# Sheet_1_MCU.net
KiCad netlist of a schematic drawn in Altium Designer
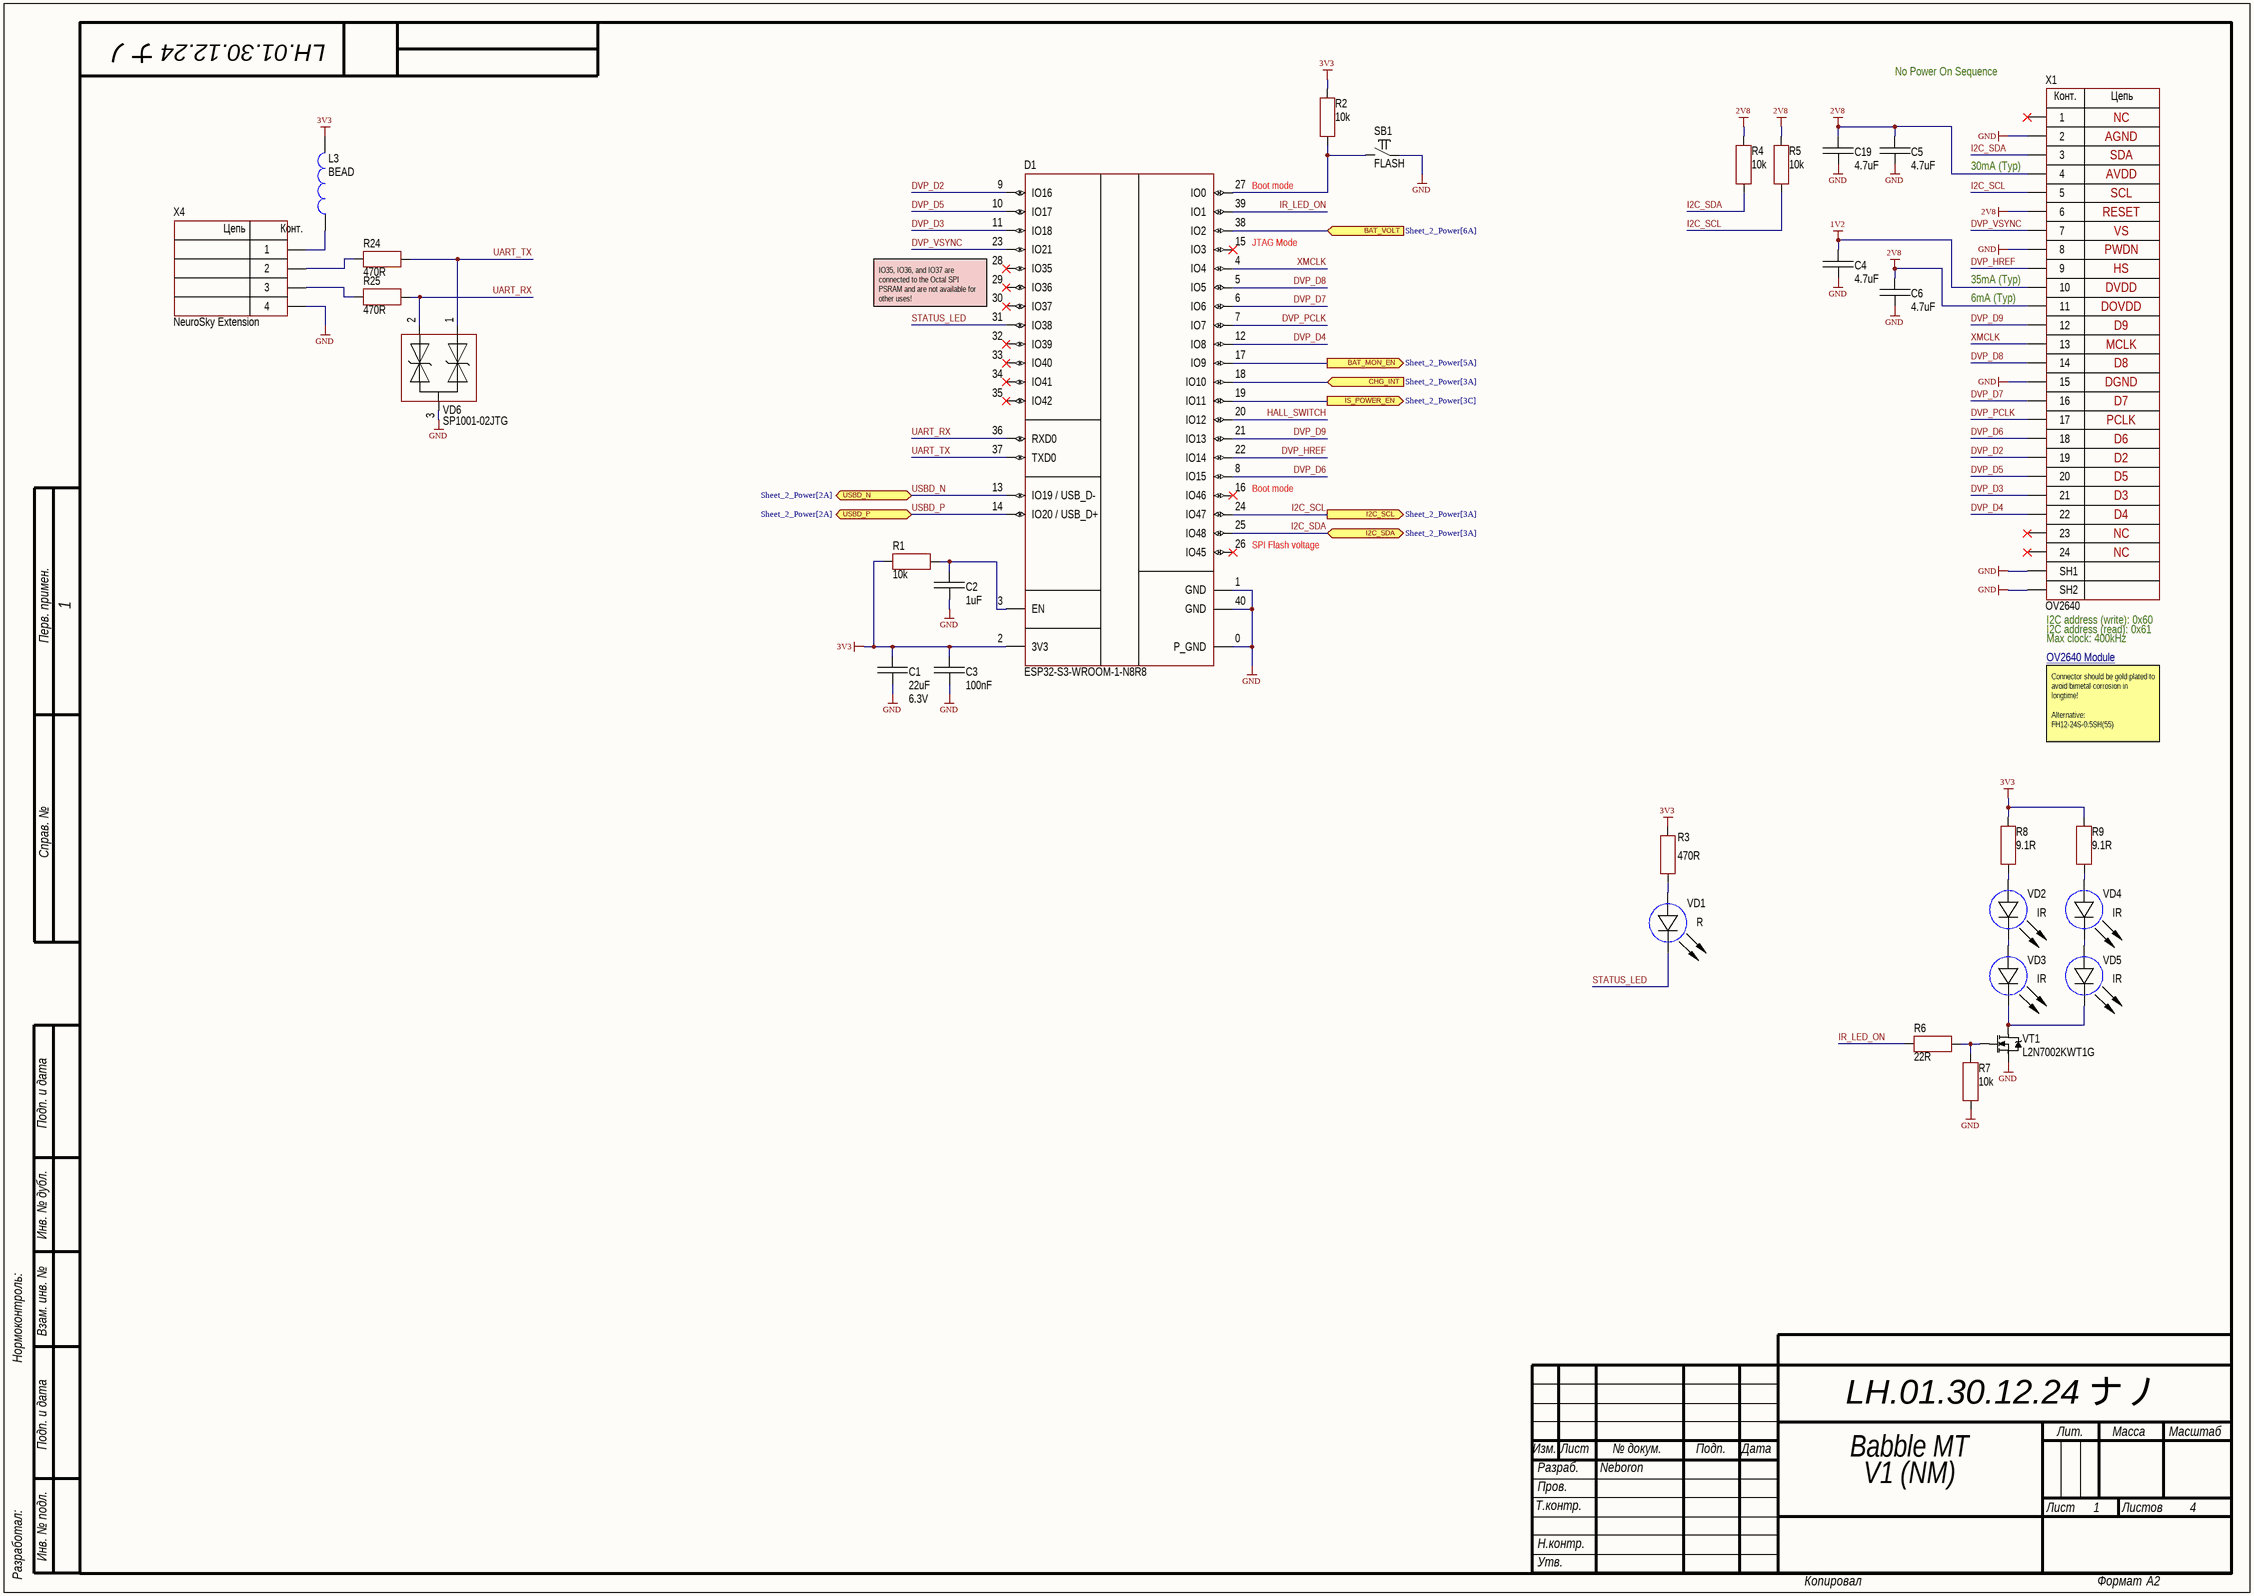
[diagram p0: Sheet_1_MCU.SchDoc]

(export (version "E")
  (design (tool "Eeschema 10.0.6"))
  (components
    (comp (ref "C1")
      (value "22uF")
      (footprint "CAP: 0603")
      (fields
        (field (name "MANUFACTURER") "Any")
        (field (name "VALUEMANUFACTURERPARTNUMBER") "Ceramic capacitor, 22uF, X5R, ±10%, 6.3V, 0603, -55...+125°C")
        (field (name "TOLERANCE") "±10%")
        (field (name "VOLTAGE") "6.3V")
      )
      (libsource (lib "capacitor") (part "Ceramic_0603"))
    )
    (comp (ref "C2")
      (value "1uF")
      (footprint "CAP: 0402")
      (fields
        (field (name "MANUFACTURER") "Any")
        (field (name "VALUEMANUFACTURERPARTNUMBER") "Ceramic capacitor, 1uF, X7R, ±10%, 6.3V, 0402, -55...+125°C")
        (field (name "TOLERANCE") "±10%")
      )
      (libsource (lib "capacitor") (part "Ceramic_0402"))
    )
    (comp (ref "C3")
      (value "100nF")
      (footprint "CAP: 0402")
      (fields
        (field (name "MANUFACTURER") "Any")
        (field (name "VALUEMANUFACTURERPARTNUMBER") "Ceramic capacitor, 100nF, X7R, ±10%, 16V, 0402, -55...+125°C")
        (field (name "TOLERANCE") "±10%")
      )
      (libsource (lib "capacitor") (part "Ceramic_0402"))
    )
    (comp (ref "C4")
      (value "4.7uF")
      (footprint "CAP: 0402")
      (fields
        (field (name "MANUFACTURER") "Any")
        (field (name "VALUEMANUFACTURERPARTNUMBER") "Ceramic capacitor, 4.7uF, X7R, ±10%, 16V, 0402, -55...+125°C")
        (field (name "TOLERANCE") "±10%")
      )
      (libsource (lib "capacitor") (part "Ceramic_0402"))
    )
    (comp (ref "C5")
      (value "4.7uF")
      (footprint "CAP: 0402")
      (fields
        (field (name "MANUFACTURER") "Any")
        (field (name "VALUEMANUFACTURERPARTNUMBER") "Ceramic capacitor, 4.7uF, X7R, ±10%, 16V, 0402, -55...+125°C")
        (field (name "TOLERANCE") "±10%")
      )
      (libsource (lib "capacitor") (part "Ceramic_0402"))
    )
    (comp (ref "C6")
      (value "4.7uF")
      (footprint "CAP: 0402")
      (fields
        (field (name "MANUFACTURER") "Any")
        (field (name "VALUEMANUFACTURERPARTNUMBER") "Ceramic capacitor, 4.7uF, X7R, ±10%, 16V, 0402, -55...+125°C")
        (field (name "TOLERANCE") "±10%")
      )
      (libsource (lib "capacitor") (part "Ceramic_0402"))
    )
    (comp (ref "C19")
      (value "4.7uF")
      (footprint "CAP: 0402")
      (fields
        (field (name "MANUFACTURER") "Any")
        (field (name "VALUEMANUFACTURERPARTNUMBER") "Ceramic capacitor, 4.7uF, X7R, ±10%, 16V, 0402, -55...+125°C")
        (field (name "TOLERANCE") "±10%")
      )
      (libsource (lib "capacitor") (part "Ceramic_0402"))
    )
    (comp (ref "D1")
      (value "~")
      (footprint "MOD: ESP32-S3-WROOM-1")
      (description "Wi-Fi")
      (fields
        (field (name "MANUFACTURER") "Espressif Systems")
        (field (name "PARTNUMBER") "ESP32-S3-WROOM-1-N8R8")
      )
      (libsource (lib "module") (part "ESP32-S3-WROOM-1-N8R8"))
    )
    (comp (ref "L3")
      (value "BEAD")
      (footprint "IND: 0402")
      (fields
        (field (name "MANUFACTURER") "Murata Electronics")
        (field (name "PARTNUMBER") "BLM15PX601SN1D")
        (field (name "VALUEMANUFACTURERPARTNUMBER") "Fixed inductor, BEAD, ±25%, 0402, 900mA, -55...+125°C")
      )
      (libsource (lib "inductor") (part "Inductor_0402"))
    )
    (comp (ref "R1")
      (value "10k")
      (footprint "RES: 0402")
      (fields
        (field (name "MANUFACTURER") "Any")
        (field (name "VALUEMANUFACTURERPARTNUMBER") "Resistor film, 10k, ±5%, 0402, 0.063W, -55...+125°C")
        (field (name "POWER") "0.063W")
      )
      (libsource (lib "") (part "Resistor_0402_2"))
    )
    (comp (ref "R2")
      (value "10k")
      (footprint "RES: 0402")
      (fields
        (field (name "MANUFACTURER") "Any")
        (field (name "VALUEMANUFACTURERPARTNUMBER") "Resistor film, 10k, ±5%, 0402, 0.063W, -55...+125°C")
        (field (name "POWER") "0.063W")
      )
      (libsource (lib "resistor") (part "Resistor_0402"))
    )
    (comp (ref "R3")
      (value "470R")
      (footprint "RES: 0402")
      (fields
        (field (name "MANUFACTURER") "Yageo")
        (field (name "PARTNUMBER") "RC0402JR-07100RL")
        (field (name "VALUEMANUFACTURERPARTNUMBER") "Resistor film, 470R, ±5%, 0402, 0.063W, -55...+125°C")
      )
      (libsource (lib "") (part "Resistor_0402_1"))
    )
    (comp (ref "R4")
      (value "10k")
      (footprint "RES: 0402")
      (fields
        (field (name "MANUFACTURER") "Any")
        (field (name "VALUEMANUFACTURERPARTNUMBER") "Resistor film, 10k, ±5%, 0402, 0.063W, -55...+125°C")
        (field (name "POWER") "0.063W")
      )
      (libsource (lib "resistor") (part "Resistor_0402"))
    )
    (comp (ref "R5")
      (value "10k")
      (footprint "RES: 0402")
      (fields
        (field (name "MANUFACTURER") "Any")
        (field (name "VALUEMANUFACTURERPARTNUMBER") "Resistor film, 10k, ±5%, 0402, 0.063W, -55...+125°C")
        (field (name "POWER") "0.063W")
      )
      (libsource (lib "resistor") (part "Resistor_0402"))
    )
    (comp (ref "R6")
      (value "22R")
      (footprint "RES: 0402")
      (fields
        (field (name "MANUFACTURER") "Any")
        (field (name "VALUEMANUFACTURERPARTNUMBER") "Resistor film, 22R, ±5%, 0402, 0.063W, -55...+125°C")
        (field (name "POWER") "0.063W")
      )
      (libsource (lib "") (part "Resistor_0402_2"))
    )
    (comp (ref "R7")
      (value "10k")
      (footprint "RES: 0402")
      (fields
        (field (name "MANUFACTURER") "Any")
        (field (name "VALUEMANUFACTURERPARTNUMBER") "Resistor film, 10k, ±5%, 0402, 0.063W, -55...+125°C")
        (field (name "POWER") "0.063W")
      )
      (libsource (lib "resistor") (part "Resistor_0402"))
    )
    (comp (ref "R8")
      (value "9.1R")
      (footprint "RES: 0603")
      (fields
        (field (name "MANUFACTURER") "Any")
        (field (name "VALUEMANUFACTURERPARTNUMBER") "Resistor film, 9.1R, ±5%, 0603, 0.1W, -55...+125°C")
        (field (name "POWER") "0.1W")
      )
      (libsource (lib "resistor") (part "Resistor_0603"))
    )
    (comp (ref "R9")
      (value "9.1R")
      (footprint "RES: 0603")
      (fields
        (field (name "MANUFACTURER") "Any")
        (field (name "VALUEMANUFACTURERPARTNUMBER") "Resistor film, 9.1R, ±5%, 0603, 0.1W, -55...+125°C")
        (field (name "POWER") "0.1W")
      )
      (libsource (lib "resistor") (part "Resistor_0603"))
    )
    (comp (ref "R24")
      (value "470R")
      (footprint "RES: 0402")
      (fields
        (field (name "MANUFACTURER") "Yageo")
        (field (name "PARTNUMBER") "RC0402JR-07100RL")
        (field (name "VALUEMANUFACTURERPARTNUMBER") "Resistor film, 470R, ±5%, 0402, 0.063W, -55...+125°C")
      )
      (libsource (lib "") (part "Resistor_0402_2"))
    )
    (comp (ref "R25")
      (value "470R")
      (footprint "RES: 0402")
      (fields
        (field (name "MANUFACTURER") "Yageo")
        (field (name "PARTNUMBER") "RC0402JR-07100RL")
        (field (name "VALUEMANUFACTURERPARTNUMBER") "Resistor film, 470R, ±5%, 0402, 0.063W, -55...+125°C")
      )
      (libsource (lib "") (part "Resistor_0402_2"))
    )
    (comp (ref "SB1")
      (value "~")
      (footprint "BUT: TS-1186F-B-A")
      (fields
        (field (name "MANUFACTURER") "XKB Connection")
        (field (name "VALUEMANUFACTURERPARTNUMBER") "Tactile button, TS-1186F")
        (field (name "PARTNUMBER") "TS-1186F-C-A")
        (field (name "COMMENTTEXT") "FLASH")
      )
      (libsource (lib "electromechanics") (part "Button_tactile"))
    )
    (comp (ref "VD1")
      (value "~")
      (footprint "LED: 0402R")
      (fields
        (field (name "VALUEMANUFACTURERPARTNUMBER") "LED, Green, *, *, *, -55...+150°C")
        (field (name "COLOR") "R")
      )
      (libsource (lib "diode") (part "LED_single"))
    )
    (comp (ref "VD2")
      (value "~")
      (footprint "LED: 1206R")
      (fields
        (field (name "MANUFACTURER") "XINGLIGHT")
        (field (name "VALUEMANUFACTURERPARTNUMBER") "LED, 850...858nm, 35mA, 1.5V, 1206, -55...+150°C")
        (field (name "PARTNUMBER") "XL-3216HIRC-850")
        (field (name "COLOR") "IR")
      )
      (libsource (lib "diode") (part "LED_single"))
    )
    (comp (ref "VD3")
      (value "~")
      (footprint "LED: 1206R")
      (fields
        (field (name "MANUFACTURER") "XINGLIGHT")
        (field (name "VALUEMANUFACTURERPARTNUMBER") "LED, 850...858nm, 35mA, 1.5V, 1206, -55...+150°C")
        (field (name "PARTNUMBER") "XL-3216HIRC-850")
        (field (name "COLOR") "IR")
      )
      (libsource (lib "diode") (part "LED_single"))
    )
    (comp (ref "VD4")
      (value "~")
      (footprint "LED: 1206R")
      (fields
        (field (name "MANUFACTURER") "XINGLIGHT")
        (field (name "VALUEMANUFACTURERPARTNUMBER") "LED, 850...858nm, 35mA, 1.5V, 1206, -55...+150°C")
        (field (name "PARTNUMBER") "XL-3216HIRC-850")
        (field (name "COLOR") "IR")
      )
      (libsource (lib "diode") (part "LED_single"))
    )
    (comp (ref "VD5")
      (value "~")
      (footprint "LED: 1206R")
      (fields
        (field (name "MANUFACTURER") "XINGLIGHT")
        (field (name "VALUEMANUFACTURERPARTNUMBER") "LED, 850...858nm, 35mA, 1.5V, 1206, -55...+150°C")
        (field (name "PARTNUMBER") "XL-3216HIRC-850")
        (field (name "COLOR") "IR")
      )
      (libsource (lib "diode") (part "LED_single"))
    )
    (comp (ref "VD6")
      (value "~")
      (footprint "SC-70")
      (fields
        (field (name "MANUFACTURER") "Littelfuse")
        (field (name "VALUEMANUFACTURERPARTNUMBER") "TVS, 5.5V, 2A, , , SC-70-3, -55...+150°C")
        (field (name "VOLTAGE") "5.5V")
        (field (name "PARTNUMBER") "SP1001-02JTG")
      )
      (libsource (lib "diode") (part "TVS_array"))
    )
    (comp (ref "VT1")
      (value "~")
      (footprint "SC-70")
      (fields
        (field (name "MANUFACTURER") "LRC")
        (field (name "VALUEMANUFACTURERPARTNUMBER") "MOSFET N-channel transistor, 60V, 380mA, , 300mW, 2.3Ohm, 34pF, SC-70, -55...+150°C")
        (field (name "PARTNUMBER") "L2N7002KWT1G")
      )
      (libsource (lib "transistor") (part "MOSFET_N_123"))
    )
    (comp (ref "X1")
      (value "~")
      (footprint "CON: FFC/FPC-24-0.5(Hirose)")
      (fields
        (field (name "MANUFACTURER") "Hirose")
        (field (name "VALUEMANUFACTURERPARTNUMBER") "Connector, 24pin, 0.5mm, FFC/FPC, 0.5A")
        (field (name "PARTNUMBER") "TF31-24S-0.5SH(800)")
        (field (name "COMMENTTEXT") "OV2640")
      )
      (libsource (lib "connector") (part "Connector_FFC_24 (TF31-24S-0.5SH(800))"))
    )
    (comp (ref "X4")
      (value "~")
      (footprint "CON: SM04B-GHS")
      (fields
        (field (name "MANUFACTURER") "JST")
        (field (name "VALUEMANUFACTURERPARTNUMBER") "Connector, 4pin, 1.25mm, 50VDC, 1A")
        (field (name "PARTNUMBER") "SM04B-GHS")
        (field (name "COMMENTTEXT") "NeuroSky Extension")
      )
      (libsource (lib "connector") (part "Connector_SM04B"))
    )
  )
  (nets
    (net (code "1") (name "/BAT_MON_EN") (class "Default")
      (node (ref "D1") (pin "17") (pinfunction "IO9_17") (pintype "bidirectional"))
    )
    (net (code "2") (name "/BAT_VOLT") (class "Default")
      (node (ref "D1") (pin "38") (pinfunction "IO2_38") (pintype "bidirectional"))
    )
    (net (code "3") (name "/CHG_INT") (class "Default")
      (node (ref "D1") (pin "18") (pinfunction "IO10_18") (pintype "bidirectional"))
    )
    (net (code "4") (name "/DVP_D2") (class "Default")
      (node (ref "D1") (pin "9") (pinfunction "IO16_9") (pintype "bidirectional"))
      (node (ref "X1") (pin "19") (pinfunction "19_19") (pintype "passive"))
    )
    (net (code "5") (name "/DVP_D3") (class "Default")
      (node (ref "D1") (pin "11") (pinfunction "IO18_11") (pintype "bidirectional"))
      (node (ref "X1") (pin "21") (pinfunction "21_21") (pintype "passive"))
    )
    (net (code "6") (name "/DVP_D4") (class "Default")
      (node (ref "D1") (pin "12") (pinfunction "IO8_12") (pintype "bidirectional"))
      (node (ref "X1") (pin "22") (pinfunction "22_22") (pintype "passive"))
    )
    (net (code "7") (name "/DVP_D5") (class "Default")
      (node (ref "D1") (pin "10") (pinfunction "IO17_10") (pintype "bidirectional"))
      (node (ref "X1") (pin "20") (pinfunction "20_20") (pintype "passive"))
    )
    (net (code "8") (name "/DVP_D6") (class "Default")
      (node (ref "D1") (pin "8") (pinfunction "IO15_8") (pintype "bidirectional"))
      (node (ref "X1") (pin "18") (pinfunction "18_18") (pintype "passive"))
    )
    (net (code "9") (name "/DVP_D7") (class "Default")
      (node (ref "D1") (pin "6") (pinfunction "IO6_6") (pintype "bidirectional"))
      (node (ref "X1") (pin "16") (pinfunction "16_16") (pintype "passive"))
    )
    (net (code "10") (name "/DVP_D8") (class "Default")
      (node (ref "D1") (pin "5") (pinfunction "IO5_5") (pintype "bidirectional"))
      (node (ref "X1") (pin "14") (pinfunction "14_14") (pintype "passive"))
    )
    (net (code "11") (name "/DVP_D9") (class "Default")
      (node (ref "D1") (pin "21") (pinfunction "IO13_21") (pintype "bidirectional"))
      (node (ref "X1") (pin "12") (pinfunction "12_12") (pintype "passive"))
    )
    (net (code "12") (name "/DVP_HREF") (class "Default")
      (node (ref "D1") (pin "22") (pinfunction "IO14_22") (pintype "bidirectional"))
      (node (ref "X1") (pin "9") (pinfunction "9_9") (pintype "passive"))
    )
    (net (code "13") (name "/DVP_PCLK") (class "Default")
      (node (ref "D1") (pin "7") (pinfunction "IO7_7") (pintype "bidirectional"))
      (node (ref "X1") (pin "17") (pinfunction "17_17") (pintype "passive"))
    )
    (net (code "14") (name "/DVP_VSYNC") (class "Default")
      (node (ref "D1") (pin "23") (pinfunction "IO21_23") (pintype "bidirectional"))
      (node (ref "X1") (pin "7") (pinfunction "7_7") (pintype "passive"))
    )
    (net (code "15") (name "/HALL_SWITCH") (class "Default")
      (node (ref "D1") (pin "20") (pinfunction "IO12_20") (pintype "bidirectional"))
    )
    (net (code "16") (name "/I2C_SCL") (class "Default")
      (node (ref "D1") (pin "24") (pinfunction "IO47_24") (pintype "bidirectional"))
      (node (ref "R5") (pin "2") (pinfunction "2_2") (pintype "passive"))
      (node (ref "X1") (pin "5") (pinfunction "5_5") (pintype "passive"))
    )
    (net (code "17") (name "/I2C_SDA") (class "Default")
      (node (ref "D1") (pin "25") (pinfunction "IO48_25") (pintype "bidirectional"))
      (node (ref "R4") (pin "2") (pinfunction "2_2") (pintype "passive"))
      (node (ref "X1") (pin "3") (pinfunction "3_3") (pintype "passive"))
    )
    (net (code "18") (name "/IR_LED_ON") (class "Default")
      (node (ref "D1") (pin "39") (pinfunction "IO1_39") (pintype "bidirectional"))
      (node (ref "R6") (pin "2") (pinfunction "2_2") (pintype "passive"))
    )
    (net (code "19") (name "/IS_POWER_EN") (class "Default")
      (node (ref "D1") (pin "19") (pinfunction "IO11_19") (pintype "bidirectional"))
    )
    (net (code "20") (name "/STATUS_LED") (class "Default")
      (node (ref "D1") (pin "31") (pinfunction "IO38_31") (pintype "bidirectional"))
      (node (ref "VD1") (pin "1") (pinfunction "C_1") (pintype "passive"))
    )
    (net (code "21") (name "/UART_RX") (class "Default")
      (node (ref "D1") (pin "36") (pinfunction "RXD0_36") (pintype "bidirectional"))
      (node (ref "R25") (pin "1") (pinfunction "1_1") (pintype "passive"))
      (node (ref "VD6") (pin "2") (pintype "passive"))
    )
    (net (code "22") (name "/UART_TX") (class "Default")
      (node (ref "D1") (pin "37") (pinfunction "TXD0_37") (pintype "bidirectional"))
      (node (ref "R24") (pin "1") (pinfunction "1_1") (pintype "passive"))
      (node (ref "VD6") (pin "1") (pintype "passive"))
    )
    (net (code "23") (name "/USBD_N") (class "Default")
      (node (ref "D1") (pin "13") (pinfunction "IO19_/_USB_D-_13") (pintype "bidirectional"))
    )
    (net (code "24") (name "/USBD_P") (class "Default")
      (node (ref "D1") (pin "14") (pinfunction "IO20_/_USB_D+_14") (pintype "bidirectional"))
    )
    (net (code "25") (name "/XMCLK") (class "Default")
      (node (ref "D1") (pin "4") (pinfunction "IO4_4") (pintype "bidirectional"))
      (node (ref "X1") (pin "13") (pinfunction "13_13") (pintype "passive"))
    )
    (net (code "26") (name "1V2") (class "Default")
      (node (ref "C4") (pin "1") (pinfunction "1_1") (pintype "passive"))
      (node (ref "X1") (pin "10") (pinfunction "10_10") (pintype "passive"))
    )
    (net (code "27") (name "2V8") (class "Default")
      (node (ref "C19") (pin "1") (pinfunction "1_1") (pintype "passive"))
      (node (ref "C5") (pin "1") (pinfunction "1_1") (pintype "passive"))
      (node (ref "C6") (pin "1") (pinfunction "1_1") (pintype "passive"))
      (node (ref "R4") (pin "1") (pinfunction "1_1") (pintype "passive"))
      (node (ref "R5") (pin "1") (pinfunction "1_1") (pintype "passive"))
      (node (ref "X1") (pin "11") (pinfunction "11_11") (pintype "passive"))
      (node (ref "X1") (pin "4") (pinfunction "4_4") (pintype "passive"))
      (node (ref "X1") (pin "6") (pinfunction "6_6") (pintype "passive"))
    )
    (net (code "28") (name "3V3") (class "Default")
      (node (ref "C1") (pin "2") (pinfunction "2_2") (pintype "passive"))
      (node (ref "C3") (pin "2") (pinfunction "2_2") (pintype "passive"))
      (node (ref "D1") (pin "2") (pinfunction "3V3_2") (pintype "power_in"))
      (node (ref "L3") (pin "1") (pinfunction "1_1") (pintype "passive"))
      (node (ref "R1") (pin "2") (pinfunction "2_2") (pintype "passive"))
      (node (ref "R2") (pin "1") (pinfunction "1_1") (pintype "passive"))
      (node (ref "R3") (pin "2") (pinfunction "2_2") (pintype "passive"))
      (node (ref "R8") (pin "2") (pinfunction "2_2") (pintype "passive"))
      (node (ref "R9") (pin "2") (pinfunction "2_2") (pintype "passive"))
    )
    (net (code "29") (name "GND") (class "Default")
      (node (ref "C1") (pin "1") (pinfunction "1_1") (pintype "passive"))
      (node (ref "C19") (pin "2") (pinfunction "2_2") (pintype "passive"))
      (node (ref "C2") (pin "1") (pinfunction "1_1") (pintype "passive"))
      (node (ref "C3") (pin "1") (pinfunction "1_1") (pintype "passive"))
      (node (ref "C4") (pin "2") (pinfunction "2_2") (pintype "passive"))
      (node (ref "C5") (pin "2") (pinfunction "2_2") (pintype "passive"))
      (node (ref "C6") (pin "2") (pinfunction "2_2") (pintype "passive"))
      (node (ref "D1") (pin "0") (pinfunction "P_GND_0") (pintype "power_in"))
      (node (ref "D1") (pin "1") (pinfunction "GND_1") (pintype "power_in"))
      (node (ref "D1") (pin "40") (pinfunction "GND_40") (pintype "power_in"))
      (node (ref "R7") (pin "2") (pinfunction "2_2") (pintype "passive"))
      (node (ref "SB1") (pin "1") (pinfunction "1_1") (pintype "passive"))
      (node (ref "VD6") (pin "3") (pintype "passive"))
      (node (ref "VT1") (pin "3") (pinfunction "S_3") (pintype "passive"))
      (node (ref "X1") (pin "15") (pinfunction "15_15") (pintype "passive"))
      (node (ref "X1") (pin "2") (pinfunction "2_2") (pintype "passive"))
      (node (ref "X1") (pin "8") (pinfunction "8_8") (pintype "passive"))
      (node (ref "X1") (pin "SH1") (pinfunction "SH1_SH1") (pintype "passive"))
      (node (ref "X1") (pin "SH2") (pinfunction "SH2_SH2") (pintype "passive"))
      (node (ref "X4") (pin "4") (pinfunction "4_4") (pintype "power_in"))
    )
    (net (code "30") (name "Net-(D1-EN)") (class "Default")
      (node (ref "C2") (pin "2") (pinfunction "2_2") (pintype "passive"))
      (node (ref "D1") (pin "3") (pinfunction "EN_3") (pintype "passive"))
      (node (ref "R1") (pin "1") (pinfunction "1_1") (pintype "passive"))
    )
    (net (code "31") (name "Net-(D1-IO0)") (class "Default")
      (node (ref "D1") (pin "27") (pinfunction "IO0_27") (pintype "bidirectional"))
      (node (ref "R2") (pin "2") (pinfunction "2_2") (pintype "passive"))
      (node (ref "SB1") (pin "2") (pinfunction "2_2") (pintype "passive"))
    )
    (net (code "32") (name "Net-(L3-Pad2)") (class "Default")
      (node (ref "L3") (pin "2") (pinfunction "2_2") (pintype "passive"))
      (node (ref "X4") (pin "1") (pinfunction "1_1") (pintype "passive"))
    )
    (net (code "33") (name "Net-(R24-Pad2)") (class "Default")
      (node (ref "R24") (pin "2") (pinfunction "2_2") (pintype "passive"))
      (node (ref "X4") (pin "2") (pinfunction "2_2") (pintype "passive"))
    )
    (net (code "34") (name "Net-(R25-Pad2)") (class "Default")
      (node (ref "R25") (pin "2") (pinfunction "2_2") (pintype "passive"))
      (node (ref "X4") (pin "3") (pinfunction "3_3") (pintype "power_in"))
    )
    (net (code "35") (name "Net-(VD1-A)") (class "Default")
      (node (ref "R3") (pin "1") (pinfunction "1_1") (pintype "passive"))
      (node (ref "VD1") (pin "2") (pinfunction "A_2") (pintype "passive"))
    )
    (net (code "36") (name "Net-(VD2-A)") (class "Default")
      (node (ref "R8") (pin "1") (pinfunction "1_1") (pintype "passive"))
      (node (ref "VD2") (pin "2") (pinfunction "A_2") (pintype "passive"))
    )
    (net (code "37") (name "Net-(VD2-C)") (class "Default")
      (node (ref "VD2") (pin "1") (pinfunction "C_1") (pintype "passive"))
      (node (ref "VD3") (pin "2") (pinfunction "A_2") (pintype "passive"))
    )
    (net (code "38") (name "Net-(VD3-C)") (class "Default")
      (node (ref "VD3") (pin "1") (pinfunction "C_1") (pintype "passive"))
      (node (ref "VD5") (pin "1") (pinfunction "C_1") (pintype "passive"))
      (node (ref "VT1") (pin "2") (pinfunction "D_2") (pintype "passive"))
    )
    (net (code "39") (name "Net-(VD4-A)") (class "Default")
      (node (ref "R9") (pin "1") (pinfunction "1_1") (pintype "passive"))
      (node (ref "VD4") (pin "2") (pinfunction "A_2") (pintype "passive"))
    )
    (net (code "40") (name "Net-(VD4-C)") (class "Default")
      (node (ref "VD4") (pin "1") (pinfunction "C_1") (pintype "passive"))
      (node (ref "VD5") (pin "2") (pinfunction "A_2") (pintype "passive"))
    )
    (net (code "41") (name "Net-(VT1-G)") (class "Default")
      (node (ref "R6") (pin "1") (pinfunction "1_1") (pintype "passive"))
      (node (ref "R7") (pin "1") (pinfunction "1_1") (pintype "passive"))
      (node (ref "VT1") (pin "1") (pinfunction "G_1") (pintype "passive"))
    )
    (net (code "42") (name "unconnected-(D1-IO3-Pad15)") (class "Default")
      (node (ref "D1") (pin "15") (pinfunction "IO3_15") (pintype "bidirectional+no_connect"))
    )
    (net (code "43") (name "unconnected-(D1-IO35-Pad28)") (class "Default")
      (node (ref "D1") (pin "28") (pinfunction "IO35_28") (pintype "bidirectional+no_connect"))
    )
    (net (code "44") (name "unconnected-(D1-IO36-Pad29)") (class "Default")
      (node (ref "D1") (pin "29") (pinfunction "IO36_29") (pintype "bidirectional+no_connect"))
    )
    (net (code "45") (name "unconnected-(D1-IO37-Pad30)") (class "Default")
      (node (ref "D1") (pin "30") (pinfunction "IO37_30") (pintype "bidirectional+no_connect"))
    )
    (net (code "46") (name "unconnected-(D1-IO39-Pad32)") (class "Default")
      (node (ref "D1") (pin "32") (pinfunction "IO39_32") (pintype "bidirectional+no_connect"))
    )
    (net (code "47") (name "unconnected-(D1-IO40-Pad33)") (class "Default")
      (node (ref "D1") (pin "33") (pinfunction "IO40_33") (pintype "bidirectional+no_connect"))
    )
    (net (code "48") (name "unconnected-(D1-IO41-Pad34)") (class "Default")
      (node (ref "D1") (pin "34") (pinfunction "IO41_34") (pintype "bidirectional+no_connect"))
    )
    (net (code "49") (name "unconnected-(D1-IO42-Pad35)") (class "Default")
      (node (ref "D1") (pin "35") (pinfunction "IO42_35") (pintype "bidirectional+no_connect"))
    )
    (net (code "50") (name "unconnected-(D1-IO45-Pad26)") (class "Default")
      (node (ref "D1") (pin "26") (pinfunction "IO45_26") (pintype "bidirectional+no_connect"))
    )
    (net (code "51") (name "unconnected-(D1-IO46-Pad16)") (class "Default")
      (node (ref "D1") (pin "16") (pinfunction "IO46_16") (pintype "bidirectional+no_connect"))
    )
    (net (code "52") (name "unconnected-(X1-Pad1)") (class "Default")
      (node (ref "X1") (pin "1") (pinfunction "1_1") (pintype "passive+no_connect"))
    )
    (net (code "53") (name "unconnected-(X1-Pad23)") (class "Default")
      (node (ref "X1") (pin "23") (pinfunction "23_23") (pintype "passive+no_connect"))
    )
    (net (code "54") (name "unconnected-(X1-Pad24)") (class "Default")
      (node (ref "X1") (pin "24") (pinfunction "24_24") (pintype "passive+no_connect"))
    )
  )
)
